# FPGA_Memory.net
KiCad netlist of a schematic drawn in Altium Designer
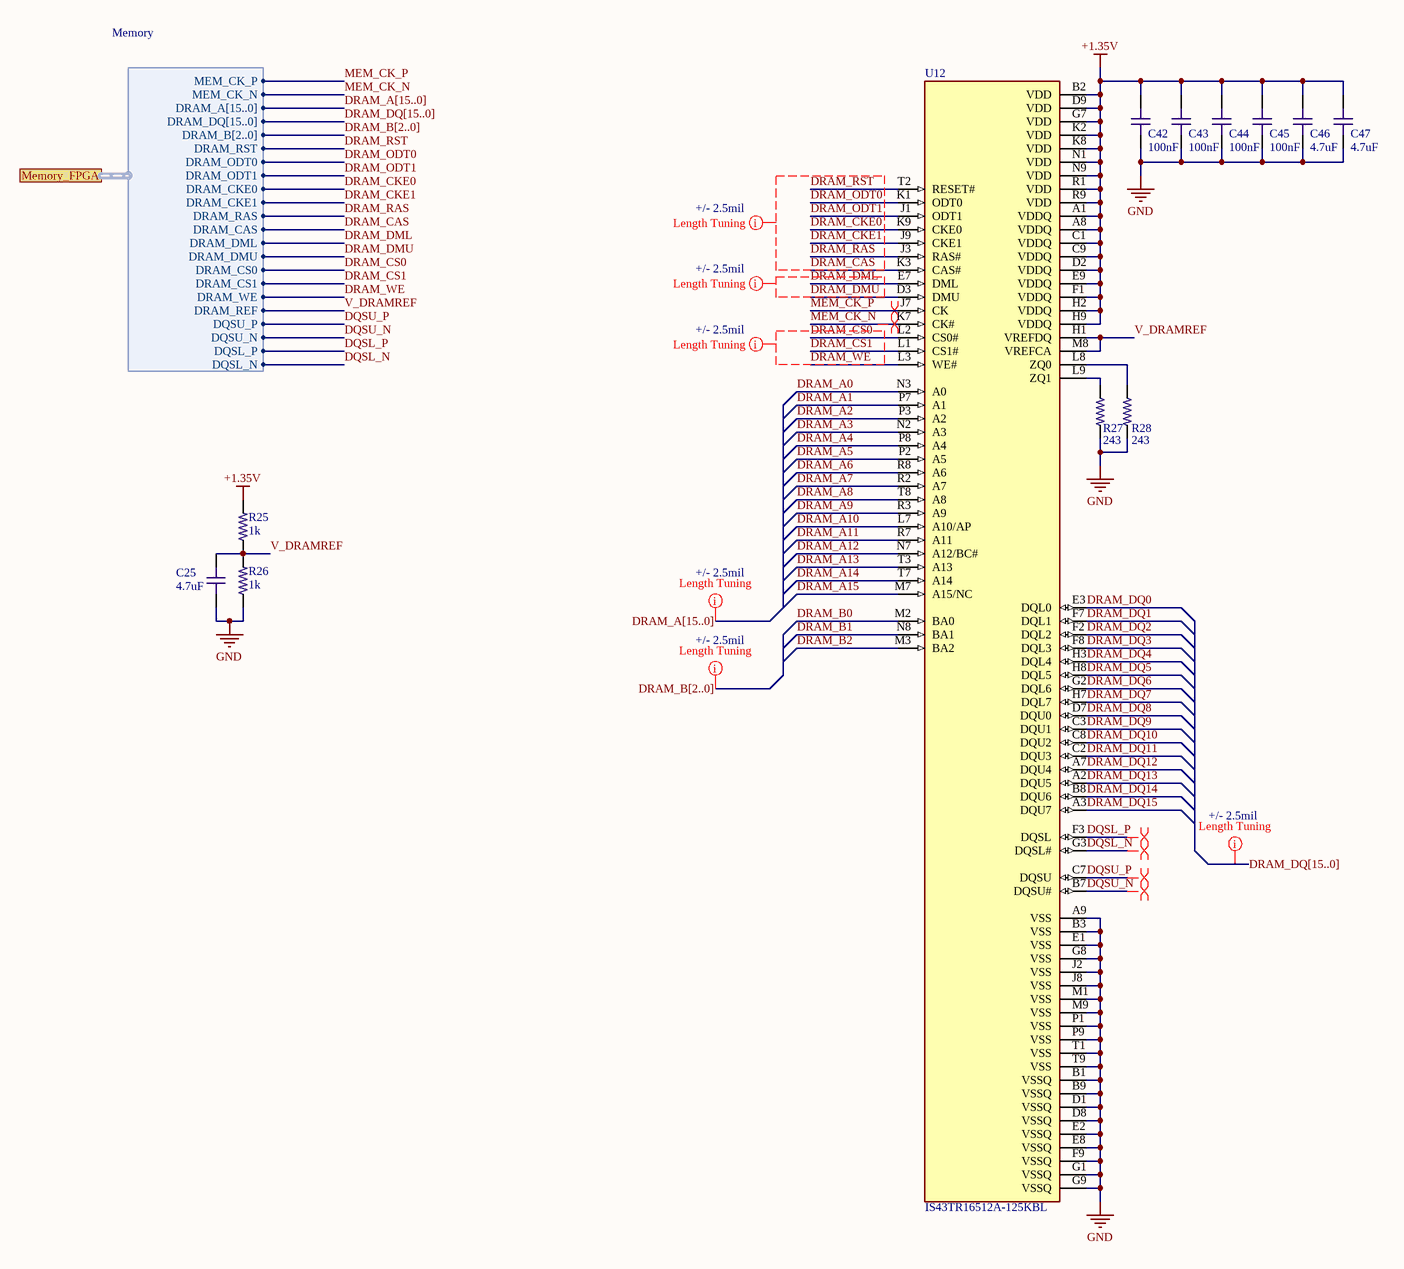
[diagram p0: FPGA_Memory.SchDoc]

(export (version "E")
  (design (tool "Eeschema 10.0.6"))
  (components
    (comp (ref "C25")
      (value "4.7uF")
      (footprint "C0603-HIGH-DENSITY")
      (description "Chip Capacitor, 0603, 4.7uF, 25V, X5R")
      (fields (field (name "Comment") "4.7uF, 25V, X5R, 0603"))
      (libsource (lib "Capacitors") (part "C0603 4.7uF 25V X5R"))
    )
    (comp (ref "C42")
      (value "100nF")
      (footprint "C0603-HIGH-DENSITY")
      (description "Chip Capacitor, 0603, 100nF, 25V, X7R")
      (fields (field (name "Comment") "C0603 100nF 25V X7R"))
      (libsource (lib "Capacitors") (part "C0603 100nF 25V X7R"))
    )
    (comp (ref "C43")
      (value "100nF")
      (footprint "C0603-HIGH-DENSITY")
      (description "Chip Capacitor, 0603, 100nF, 25V, X7R")
      (fields (field (name "Comment") "C0603 100nF 25V X7R"))
      (libsource (lib "Capacitors") (part "C0603 100nF 25V X7R"))
    )
    (comp (ref "C44")
      (value "100nF")
      (footprint "C0603-HIGH-DENSITY")
      (description "Chip Capacitor, 0603, 100nF, 25V, X7R")
      (fields (field (name "Comment") "C0603 100nF 25V X7R"))
      (libsource (lib "Capacitors") (part "C0603 100nF 25V X7R"))
    )
    (comp (ref "C45")
      (value "100nF")
      (footprint "C0603-HIGH-DENSITY")
      (description "Chip Capacitor, 0603, 100nF, 25V, X7R")
      (fields (field (name "Comment") "C0603 100nF 25V X7R"))
      (libsource (lib "Capacitors") (part "C0603 100nF 25V X7R"))
    )
    (comp (ref "C46")
      (value "4.7uF")
      (footprint "C0603-HIGH-DENSITY")
      (description "Chip Capacitor, 0603, 4.7uF, 25V, X5R")
      (fields (field (name "Comment") "4.7uF, 25V, X5R, 0603"))
      (libsource (lib "Capacitors") (part "C0603 4.7uF 25V X5R"))
    )
    (comp (ref "C47")
      (value "4.7uF")
      (footprint "C0603-HIGH-DENSITY")
      (description "Chip Capacitor, 0603, 4.7uF, 25V, X5R")
      (fields (field (name "Comment") "4.7uF, 25V, X5R, 0603"))
      (libsource (lib "Capacitors") (part "C0603 4.7uF 25V X5R"))
    )
    (comp (ref "R25")
      (value "1k")
      (footprint "R0603-IPC-1K")
      (description "RES SMD 1K OHM 1% 1/10W 0603")
      (fields (field (name "TOLERANCE") "±1%") (field (name "Comment") "R0603 1K 1%"))
      (libsource (lib "Resistors") (part "R0603 1K 1%"))
    )
    (comp (ref "R26")
      (value "1k")
      (footprint "R0603-IPC-1K")
      (description "RES SMD 1K OHM 1% 1/10W 0603")
      (fields (field (name "TOLERANCE") "±1%") (field (name "Comment") "R0603 1K 1%"))
      (libsource (lib "Resistors") (part "R0603 1K 1%"))
    )
    (comp (ref "R27")
      (value "243")
      (footprint "R0603-IPC")
      (description "RES SMD 243 OHM 1% 1/10W 0603")
      (fields (field (name "TOLERANCE") "±1%") (field (name "Comment") "R0603 243 1%"))
      (libsource (lib "Resistors") (part "R0603 243 1%"))
    )
    (comp (ref "R28")
      (value "243")
      (footprint "R0603-IPC")
      (description "RES SMD 243 OHM 1% 1/10W 0603")
      (fields (field (name "TOLERANCE") "±1%") (field (name "Comment") "R0603 243 1%"))
      (libsource (lib "Resistors") (part "R0603 243 1%"))
    )
    (comp (ref "U12")
      (value "IS43TR16512A-125KBL")
      (footprint "BGA96C80P9X16_1000X1400X140N")
      (description "SDRAM - DDR3L Memory IC 8Gb (512M x 16) Parallel 800MHz 20ns 96-LFBGA (10x14)")
      (fields (field (name "MF") "ISSI, Integrated") (field (name "MP") "IS43TR16512AL-125KBL"))
      (libsource (lib "Integrated Circuits") (part "IS43TR16512A/L-125KBL"))
    )
  )
  (nets
    (net (code "2") (name "+1.35V") (class "Default")
      (node (ref "C42") (pin "2") (pintype "passive"))
      (node (ref "C43") (pin "2") (pintype "passive"))
      (node (ref "C44") (pin "2") (pintype "passive"))
      (node (ref "C45") (pin "2") (pintype "passive"))
      (node (ref "C46") (pin "2") (pintype "passive"))
      (node (ref "C47") (pin "2") (pintype "passive"))
      (node (ref "R25") (pin "2") (pintype "passive"))
      (node (ref "U12") (pin "A1") (pinfunction "VDDQ_A1") (pintype "power_in"))
      (node (ref "U12") (pin "A8") (pinfunction "VDDQ_A8") (pintype "power_in"))
      (node (ref "U12") (pin "B2") (pinfunction "VDD_B2") (pintype "power_in"))
      (node (ref "U12") (pin "C1") (pinfunction "VDDQ_C1") (pintype "power_in"))
      (node (ref "U12") (pin "C9") (pinfunction "VDDQ_C9") (pintype "power_in"))
      (node (ref "U12") (pin "D2") (pinfunction "VDDQ_D2") (pintype "power_in"))
      (node (ref "U12") (pin "D9") (pinfunction "VDD_D9") (pintype "power_in"))
      (node (ref "U12") (pin "E9") (pinfunction "VDDQ_E9") (pintype "power_in"))
      (node (ref "U12") (pin "F1") (pinfunction "VDDQ_F1") (pintype "power_in"))
      (node (ref "U12") (pin "G7") (pinfunction "VDD_G7") (pintype "power_in"))
      (node (ref "U12") (pin "H2") (pinfunction "VDDQ_H2") (pintype "power_in"))
      (node (ref "U12") (pin "H9") (pinfunction "VDDQ_H9") (pintype "power_in"))
      (node (ref "U12") (pin "K2") (pinfunction "VDD_K2") (pintype "power_in"))
      (node (ref "U12") (pin "K8") (pinfunction "VDD_K8") (pintype "power_in"))
      (node (ref "U12") (pin "N1") (pinfunction "VDD_N1") (pintype "power_in"))
      (node (ref "U12") (pin "N9") (pinfunction "VDD_N9") (pintype "power_in"))
      (node (ref "U12") (pin "R1") (pinfunction "VDD_R1") (pintype "power_in"))
      (node (ref "U12") (pin "R9") (pinfunction "VDD_R9") (pintype "power_in"))
    )
    (net (code "3") (name "/DQSL_N") (class "Default")
      (node (ref "U12") (pin "G3") (pinfunction "DQSL#_G3") (pintype "bidirectional"))
    )
    (net (code "4") (name "/DQSL_P") (class "Default")
      (node (ref "U12") (pin "F3") (pinfunction "DQSL_F3") (pintype "bidirectional"))
    )
    (net (code "5") (name "/DQSU_N") (class "Default")
      (node (ref "U12") (pin "B7") (pinfunction "DQSU#_B7") (pintype "bidirectional"))
    )
    (net (code "6") (name "/DQSU_P") (class "Default")
      (node (ref "U12") (pin "C7") (pinfunction "DQSU_C7") (pintype "bidirectional"))
    )
    (net (code "7") (name "/DRAM_A0") (class "Default")
      (node (ref "U12") (pin "N3") (pinfunction "A0_N3") (pintype "input"))
    )
    (net (code "8") (name "/DRAM_A1") (class "Default")
      (node (ref "U12") (pin "P7") (pinfunction "A1_P7") (pintype "input"))
    )
    (net (code "9") (name "/DRAM_A2") (class "Default")
      (node (ref "U12") (pin "P3") (pinfunction "A2_P3") (pintype "input"))
    )
    (net (code "10") (name "/DRAM_A3") (class "Default")
      (node (ref "U12") (pin "N2") (pinfunction "A3_N2") (pintype "input"))
    )
    (net (code "11") (name "/DRAM_A4") (class "Default")
      (node (ref "U12") (pin "P8") (pinfunction "A4_P8") (pintype "input"))
    )
    (net (code "12") (name "/DRAM_A5") (class "Default")
      (node (ref "U12") (pin "P2") (pinfunction "A5_P2") (pintype "input"))
    )
    (net (code "13") (name "/DRAM_A6") (class "Default")
      (node (ref "U12") (pin "R8") (pinfunction "A6_R8") (pintype "input"))
    )
    (net (code "14") (name "/DRAM_A7") (class "Default")
      (node (ref "U12") (pin "R2") (pinfunction "A7_R2") (pintype "input"))
    )
    (net (code "15") (name "/DRAM_A8") (class "Default")
      (node (ref "U12") (pin "T8") (pinfunction "A8_T8") (pintype "input"))
    )
    (net (code "16") (name "/DRAM_A9") (class "Default")
      (node (ref "U12") (pin "R3") (pinfunction "A9_R3") (pintype "input"))
    )
    (net (code "17") (name "/DRAM_A10") (class "Default")
      (node (ref "U12") (pin "L7") (pinfunction "A10/AP_L7") (pintype "input"))
    )
    (net (code "18") (name "/DRAM_A11") (class "Default")
      (node (ref "U12") (pin "R7") (pinfunction "A11_R7") (pintype "input"))
    )
    (net (code "19") (name "/DRAM_A12") (class "Default")
      (node (ref "U12") (pin "N7") (pinfunction "A12/BC#_N7") (pintype "input"))
    )
    (net (code "20") (name "/DRAM_A13") (class "Default")
      (node (ref "U12") (pin "T3") (pinfunction "A13_T3") (pintype "input"))
    )
    (net (code "21") (name "/DRAM_A14") (class "Default")
      (node (ref "U12") (pin "T7") (pinfunction "A14_T7") (pintype "input"))
    )
    (net (code "22") (name "/DRAM_A15") (class "Default")
      (node (ref "U12") (pin "M7") (pinfunction "A15/NC_M7") (pintype "input"))
    )
    (net (code "24") (name "/DRAM_B0") (class "Default")
      (node (ref "U12") (pin "M2") (pinfunction "BA0_M2") (pintype "input"))
    )
    (net (code "25") (name "/DRAM_B1") (class "Default")
      (node (ref "U12") (pin "N8") (pinfunction "BA1_N8") (pintype "input"))
    )
    (net (code "26") (name "/DRAM_B2") (class "Default")
      (node (ref "U12") (pin "M3") (pinfunction "BA2_M3") (pintype "input"))
    )
    (net (code "28") (name "/DRAM_CAS") (class "Default")
      (node (ref "U12") (pin "K3") (pinfunction "CAS#_K3") (pintype "input"))
    )
    (net (code "29") (name "/DRAM_CKE0") (class "Default")
      (node (ref "U12") (pin "K9") (pinfunction "CKE0_K9") (pintype "input"))
    )
    (net (code "30") (name "/DRAM_CKE1") (class "Default")
      (node (ref "U12") (pin "J9") (pinfunction "CKE1_J9") (pintype "input"))
    )
    (net (code "31") (name "/DRAM_CS0") (class "Default")
      (node (ref "U12") (pin "L2") (pinfunction "CS0#_L2") (pintype "input"))
    )
    (net (code "32") (name "/DRAM_CS1") (class "Default")
      (node (ref "U12") (pin "L1") (pinfunction "CS1#_L1") (pintype "input"))
    )
    (net (code "33") (name "/DRAM_DML") (class "Default")
      (node (ref "U12") (pin "E7") (pinfunction "DML_E7") (pintype "input"))
    )
    (net (code "34") (name "/DRAM_DMU") (class "Default")
      (node (ref "U12") (pin "D3") (pinfunction "DMU_D3") (pintype "input"))
    )
    (net (code "35") (name "/DRAM_DQ0") (class "Default")
      (node (ref "U12") (pin "E3") (pinfunction "DQL0_E3") (pintype "bidirectional"))
    )
    (net (code "36") (name "/DRAM_DQ1") (class "Default")
      (node (ref "U12") (pin "F7") (pinfunction "DQL1_F7") (pintype "bidirectional"))
    )
    (net (code "37") (name "/DRAM_DQ2") (class "Default")
      (node (ref "U12") (pin "F2") (pinfunction "DQL2_F2") (pintype "bidirectional"))
    )
    (net (code "38") (name "/DRAM_DQ3") (class "Default")
      (node (ref "U12") (pin "F8") (pinfunction "DQL3_F8") (pintype "bidirectional"))
    )
    (net (code "39") (name "/DRAM_DQ4") (class "Default")
      (node (ref "U12") (pin "H3") (pinfunction "DQL4_H3") (pintype "bidirectional"))
    )
    (net (code "40") (name "/DRAM_DQ5") (class "Default")
      (node (ref "U12") (pin "H8") (pinfunction "DQL5_H8") (pintype "bidirectional"))
    )
    (net (code "41") (name "/DRAM_DQ6") (class "Default")
      (node (ref "U12") (pin "G2") (pinfunction "DQL6_G2") (pintype "bidirectional"))
    )
    (net (code "42") (name "/DRAM_DQ7") (class "Default")
      (node (ref "U12") (pin "H7") (pinfunction "DQL7_H7") (pintype "bidirectional"))
    )
    (net (code "43") (name "/DRAM_DQ8") (class "Default")
      (node (ref "U12") (pin "D7") (pinfunction "DQU0_D7") (pintype "bidirectional"))
    )
    (net (code "44") (name "/DRAM_DQ9") (class "Default")
      (node (ref "U12") (pin "C3") (pinfunction "DQU1_C3") (pintype "bidirectional"))
    )
    (net (code "45") (name "/DRAM_DQ10") (class "Default")
      (node (ref "U12") (pin "C8") (pinfunction "DQU2_C8") (pintype "bidirectional"))
    )
    (net (code "46") (name "/DRAM_DQ11") (class "Default")
      (node (ref "U12") (pin "C2") (pinfunction "DQU3_C2") (pintype "bidirectional"))
    )
    (net (code "47") (name "/DRAM_DQ12") (class "Default")
      (node (ref "U12") (pin "A7") (pinfunction "DQU4_A7") (pintype "bidirectional"))
    )
    (net (code "48") (name "/DRAM_DQ13") (class "Default")
      (node (ref "U12") (pin "A2") (pinfunction "DQU5_A2") (pintype "bidirectional"))
    )
    (net (code "49") (name "/DRAM_DQ14") (class "Default")
      (node (ref "U12") (pin "B8") (pinfunction "DQU6_B8") (pintype "bidirectional"))
    )
    (net (code "50") (name "/DRAM_DQ15") (class "Default")
      (node (ref "U12") (pin "A3") (pinfunction "DQU7_A3") (pintype "bidirectional"))
    )
    (net (code "52") (name "/DRAM_ODT0") (class "Default")
      (node (ref "U12") (pin "K1") (pinfunction "ODT0_K1") (pintype "input"))
    )
    (net (code "53") (name "/DRAM_ODT1") (class "Default")
      (node (ref "U12") (pin "J1") (pinfunction "ODT1_J1") (pintype "input"))
    )
    (net (code "54") (name "/DRAM_RAS") (class "Default")
      (node (ref "U12") (pin "J3") (pinfunction "RAS#_J3") (pintype "input"))
    )
    (net (code "55") (name "/DRAM_RST") (class "Default")
      (node (ref "U12") (pin "T2") (pinfunction "RESET#_T2") (pintype "input"))
    )
    (net (code "56") (name "/DRAM_WE") (class "Default")
      (node (ref "U12") (pin "L3") (pinfunction "WE#_L3") (pintype "input"))
    )
    (net (code "57") (name "/MEM_CK_N") (class "Default")
      (node (ref "U12") (pin "K7") (pinfunction "CK#_K7") (pintype "input"))
    )
    (net (code "58") (name "/MEM_CK_P") (class "Default")
      (node (ref "U12") (pin "J7") (pinfunction "CK_J7") (pintype "input"))
    )
    (net (code "59") (name "/V_DRAMREF") (class "Default")
      (node (ref "C25") (pin "2") (pintype "passive"))
      (node (ref "R25") (pin "1") (pintype "passive"))
      (node (ref "R26") (pin "2") (pintype "passive"))
      (node (ref "U12") (pin "H1") (pinfunction "VREFDQ_H1") (pintype "power_in"))
      (node (ref "U12") (pin "M8") (pinfunction "VREFCA_M8") (pintype "power_in"))
    )
    (net (code "61") (name "GND") (class "Default")
      (node (ref "C25") (pin "1") (pintype "passive"))
      (node (ref "C42") (pin "1") (pintype "passive"))
      (node (ref "C43") (pin "1") (pintype "passive"))
      (node (ref "C44") (pin "1") (pintype "passive"))
      (node (ref "C45") (pin "1") (pintype "passive"))
      (node (ref "C46") (pin "1") (pintype "passive"))
      (node (ref "C47") (pin "1") (pintype "passive"))
      (node (ref "R26") (pin "1") (pintype "passive"))
      (node (ref "R27") (pin "2") (pintype "passive"))
      (node (ref "R28") (pin "2") (pintype "passive"))
      (node (ref "U12") (pin "A9") (pinfunction "VSS_A9") (pintype "power_in"))
      (node (ref "U12") (pin "B1") (pinfunction "VSSQ_B1") (pintype "power_in"))
      (node (ref "U12") (pin "B3") (pinfunction "VSS_B3") (pintype "power_in"))
      (node (ref "U12") (pin "B9") (pinfunction "VSSQ_B9") (pintype "power_in"))
      (node (ref "U12") (pin "D1") (pinfunction "VSSQ_D1") (pintype "power_in"))
      (node (ref "U12") (pin "D8") (pinfunction "VSSQ_D8") (pintype "power_in"))
      (node (ref "U12") (pin "E1") (pinfunction "VSS_E1") (pintype "power_in"))
      (node (ref "U12") (pin "E2") (pinfunction "VSSQ_E2") (pintype "power_in"))
      (node (ref "U12") (pin "E8") (pinfunction "VSSQ_E8") (pintype "power_in"))
      (node (ref "U12") (pin "F9") (pinfunction "VSSQ_F9") (pintype "power_in"))
      (node (ref "U12") (pin "G1") (pinfunction "VSSQ_G1") (pintype "power_in"))
      (node (ref "U12") (pin "G8") (pinfunction "VSS_G8") (pintype "power_in"))
      (node (ref "U12") (pin "G9") (pinfunction "VSSQ_G9") (pintype "power_in"))
      (node (ref "U12") (pin "J2") (pinfunction "VSS_J2") (pintype "power_in"))
      (node (ref "U12") (pin "J8") (pinfunction "VSS_J8") (pintype "power_in"))
      (node (ref "U12") (pin "M1") (pinfunction "VSS_M1") (pintype "power_in"))
      (node (ref "U12") (pin "M9") (pinfunction "VSS_M9") (pintype "power_in"))
      (node (ref "U12") (pin "P1") (pinfunction "VSS_P1") (pintype "power_in"))
      (node (ref "U12") (pin "P9") (pinfunction "VSS_P9") (pintype "power_in"))
      (node (ref "U12") (pin "T1") (pinfunction "VSS_T1") (pintype "power_in"))
      (node (ref "U12") (pin "T9") (pinfunction "VSS_T9") (pintype "power_in"))
    )
    (net (code "62") (name "Net-(U12-ZQ0)") (class "Default")
      (node (ref "R28") (pin "1") (pintype "passive"))
      (node (ref "U12") (pin "L8") (pinfunction "ZQ0_L8") (pintype "power_in"))
    )
    (net (code "63") (name "Net-(U12-ZQ1)") (class "Default")
      (node (ref "R27") (pin "1") (pintype "passive"))
      (node (ref "U12") (pin "L9") (pinfunction "ZQ1_L9") (pintype "power_in"))
    )
  )
)
